# Hot_tub_PoE_RS485_Arduino.net
KiCad netlist of a schematic drawn in EAGLE
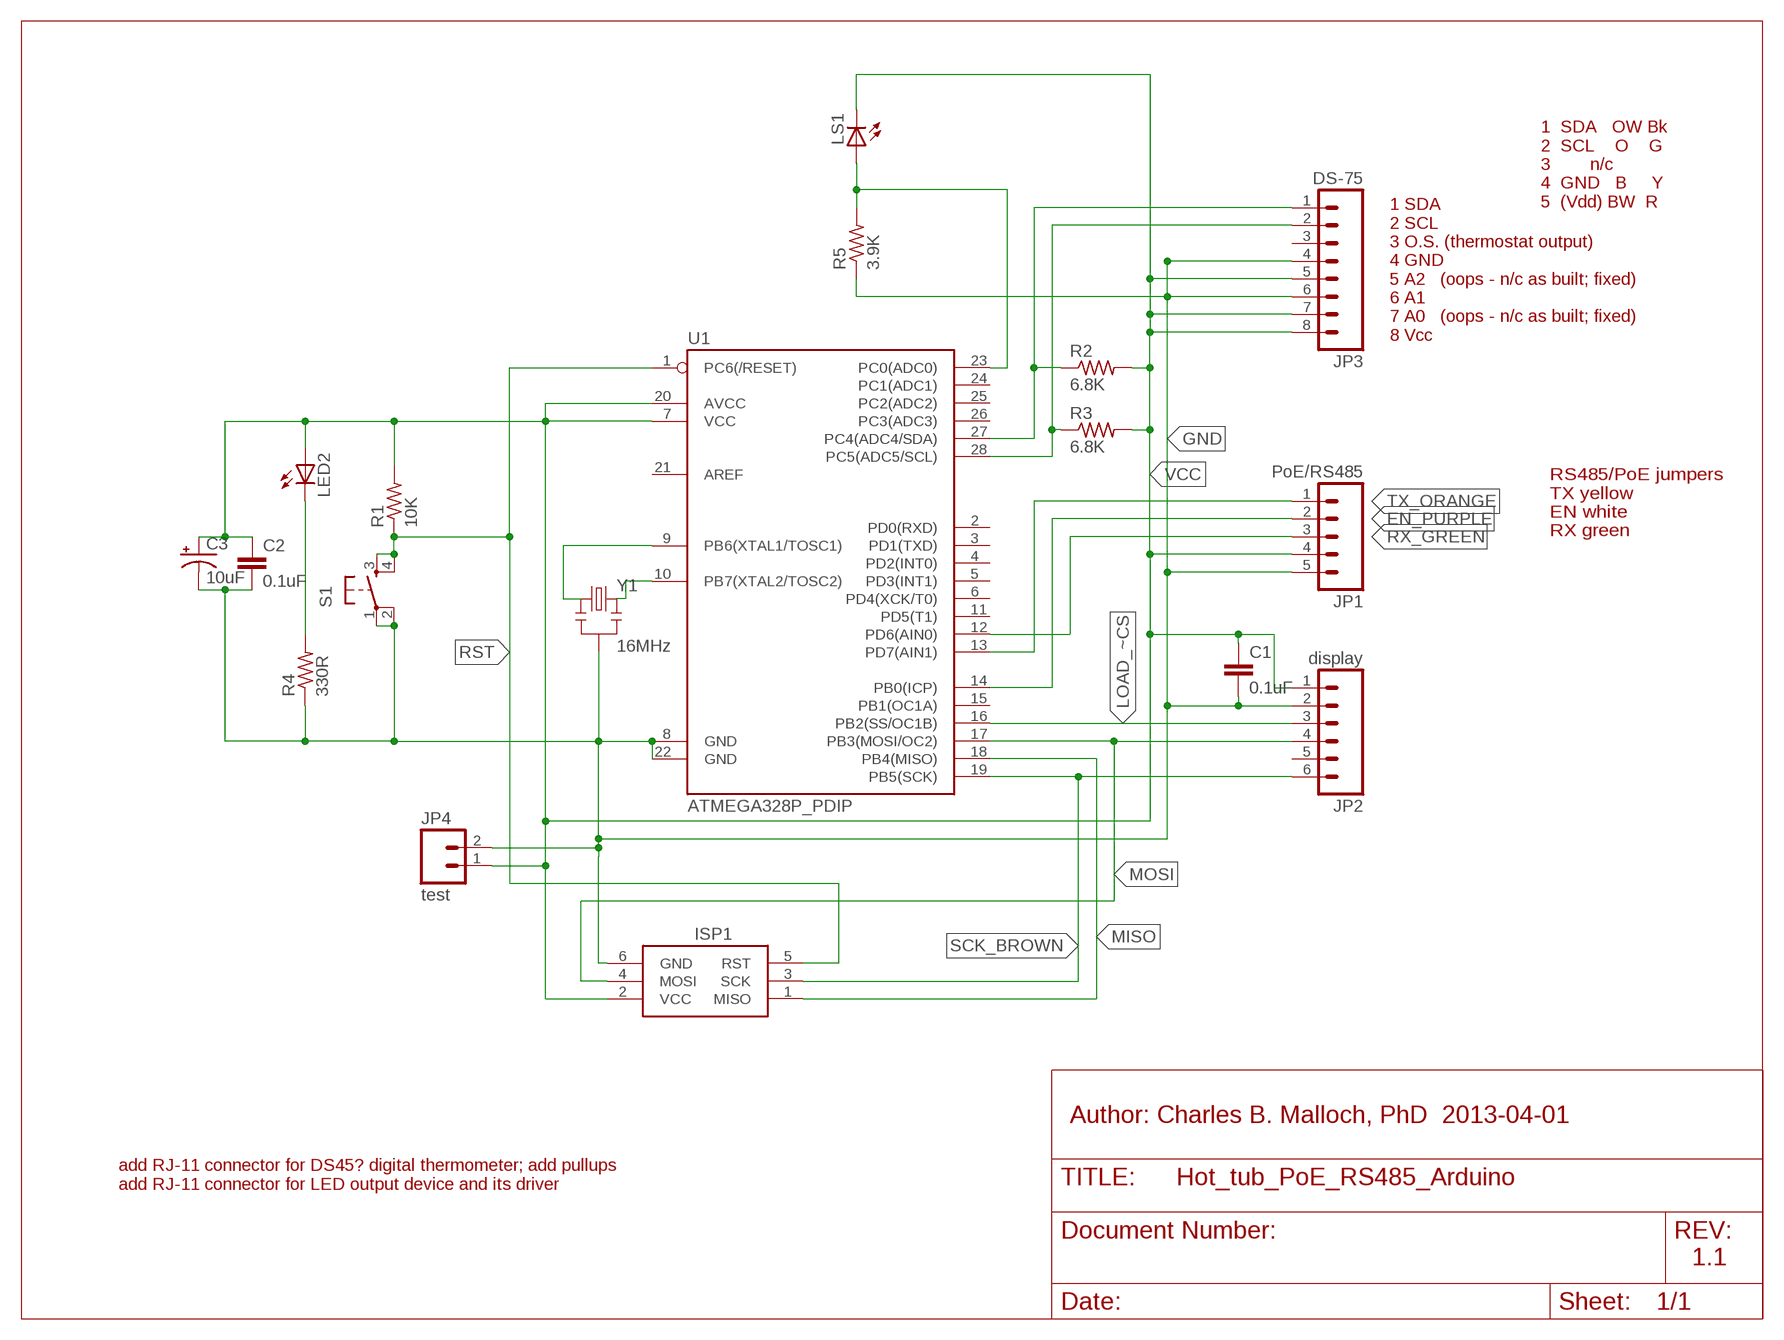
[diagram p0: schematic, sheet 1]

(export (version "E")
  (design (tool "Eeschema 10.0.6"))
  (components
    (comp (ref "C1")
      (value "0.1uF")
      (footprint "eagle-import:CAP-PTH-SMALL")
      (libsource (lib "eagle-import") (part "CAPPTH"))
    )
    (comp (ref "C2")
      (value "0.1uF")
      (footprint "eagle-import:CAP-PTH-SMALL")
      (libsource (lib "eagle-import") (part "CAPPTH"))
    )
    (comp (ref "C3")
      (value "10uF")
      (footprint "eagle-import:CPOL-RADIAL-10UF-25V")
      (libsource (lib "eagle-import") (part "CAP_POLPTH2"))
    )
    (comp (ref "ISP1")
      (value "AVRISP-6")
      (footprint "eagle-import:AVRISP")
      (libsource (lib "eagle-import") (part "AVRISP-6"))
    )
    (comp (ref "JP1")
      (value "PoE/RS485")
      (footprint "eagle-import:1X05_LOCK_LONGPADS")
      (libsource (lib "eagle-import") (part "M05LOCK_LONGPADS"))
    )
    (comp (ref "JP2")
      (value "display")
      (footprint "eagle-import:1X06_LOCK_LONGPADS")
      (libsource (lib "eagle-import") (part "M06LOCK_LONGPADS"))
    )
    (comp (ref "JP3")
      (value "DS-75")
      (footprint "eagle-import:1X08_LOCK_LONGPADS")
      (libsource (lib "eagle-import") (part "M08LOCK_LONGPADS"))
    )
    (comp (ref "JP4")
      (value "test")
      (footprint "eagle-import:1X02_LOCK_LONGPADS")
      (libsource (lib "eagle-import") (part "M02LOCK_LONGPADS"))
    )
    (comp (ref "LED2")
      (value "LED5MM")
      (footprint "eagle-import:LED5MM")
      (libsource (lib "eagle-import") (part "LED5MM"))
    )
    (comp (ref "LS1")
      (value "LED5MM")
      (footprint "eagle-import:LED5MM")
      (libsource (lib "eagle-import") (part "LED5MM"))
    )
    (comp (ref "R1")
      (value "10K")
      (footprint "eagle-import:0204_5")
      (libsource (lib "eagle-import") (part "R-US_0204/5"))
    )
    (comp (ref "R2")
      (value "6.8K")
      (footprint "eagle-import:0207_10")
      (libsource (lib "eagle-import") (part "resistor_R-US_0207/10"))
    )
    (comp (ref "R3")
      (value "6.8K")
      (footprint "eagle-import:0207_10")
      (libsource (lib "eagle-import") (part "resistor_R-US_0207/10"))
    )
    (comp (ref "R4")
      (value "330R")
      (footprint "eagle-import:0207_10")
      (libsource (lib "eagle-import") (part "resistor_R-US_0207/10"))
    )
    (comp (ref "R5")
      (value "3.9K")
      (footprint "eagle-import:0207_10")
      (libsource (lib "eagle-import") (part "resistor_R-US_0207/10"))
    )
    (comp (ref "S1")
      (value "TAC_SWITCHPTH")
      (footprint "eagle-import:TACTILE-PTH")
      (libsource (lib "eagle-import") (part "TAC_SWITCHPTH"))
    )
    (comp (ref "U1")
      (value "ATMEGA328P_PDIP")
      (footprint "eagle-import:DIL28-3")
      (libsource (lib "eagle-import") (part "ATMEGA328P_PDIP"))
    )
    (comp (ref "Y1")
      (value "16MHz")
      (footprint "eagle-import:RESONATOR-PTH")
      (libsource (lib "eagle-import") (part "RESONATORPTH"))
    )
  )
  (nets
    (net (code "1") (name "/LOAD_~{CS}") (class "Default")
      (node (ref "JP2") (pin "3") (pinfunction "3_3") (pintype "passive"))
      (node (ref "U1") (pin "16") (pinfunction "PB2(SS/OC1B)_16") (pintype "bidirectional"))
    )
    (net (code "2") (name "EN_PURPLE") (class "Default")
      (node (ref "JP1") (pin "2") (pinfunction "2_2") (pintype "passive"))
      (node (ref "U1") (pin "14") (pinfunction "PB0(ICP)_14") (pintype "bidirectional"))
    )
    (net (code "3") (name "GND") (class "Default")
      (node (ref "C1") (pin "2") (pinfunction "2_2") (pintype "passive"))
      (node (ref "C2") (pin "2") (pinfunction "2_2") (pintype "passive"))
      (node (ref "C3") (pin "2") (pinfunction "-_2") (pintype "passive"))
      (node (ref "ISP1") (pin "6") (pinfunction "GND_6") (pintype "power_in"))
      (node (ref "JP1") (pin "5") (pinfunction "5_5") (pintype "passive"))
      (node (ref "JP2") (pin "2") (pinfunction "2_2") (pintype "passive"))
      (node (ref "JP3") (pin "4") (pinfunction "4_4") (pintype "passive"))
      (node (ref "JP3") (pin "6") (pinfunction "6_6") (pintype "passive"))
      (node (ref "JP4") (pin "2") (pinfunction "2_2") (pintype "passive"))
      (node (ref "R4") (pin "1") (pinfunction "1_1") (pintype "passive"))
      (node (ref "R5") (pin "1") (pinfunction "1_1") (pintype "passive"))
      (node (ref "S1") (pin "1") (pinfunction "1_1") (pintype "passive"))
      (node (ref "S1") (pin "2") (pinfunction "2_2") (pintype "passive"))
      (node (ref "U1") (pin "22") (pinfunction "GND_22") (pintype "bidirectional"))
      (node (ref "U1") (pin "8") (pinfunction "GND_8") (pintype "bidirectional"))
      (node (ref "Y1") (pin "2") (pinfunction "2_2") (pintype "passive"))
    )
    (net (code "4") (name "MISO") (class "Default")
      (node (ref "ISP1") (pin "1") (pinfunction "MISO_1") (pintype "input"))
      (node (ref "U1") (pin "18") (pinfunction "PB4(MISO)_18") (pintype "bidirectional"))
    )
    (net (code "5") (name "MOSI") (class "Default")
      (node (ref "ISP1") (pin "4") (pinfunction "MOSI_4") (pintype "output"))
      (node (ref "JP2") (pin "4") (pinfunction "4_4") (pintype "passive"))
      (node (ref "U1") (pin "17") (pinfunction "PB3(MOSI/OC2)_17") (pintype "bidirectional"))
    )
    (net (code "6") (name "Net-(LED2-C)") (class "Default")
      (node (ref "LED2") (pin "K") (pinfunction "C_K") (pintype "passive"))
      (node (ref "R4") (pin "2") (pinfunction "2_2") (pintype "passive"))
    )
    (net (code "7") (name "Net-(U1-PB6(XTAL1{slash}TOSC1))") (class "Default")
      (node (ref "U1") (pin "9") (pinfunction "PB6(XTAL1/TOSC1)_9") (pintype "bidirectional"))
      (node (ref "Y1") (pin "1") (pinfunction "1_1") (pintype "passive"))
    )
    (net (code "8") (name "Net-(U1-PB7(XTAL2{slash}TOSC2))") (class "Default")
      (node (ref "U1") (pin "10") (pinfunction "PB7(XTAL2/TOSC2)_10") (pintype "bidirectional"))
      (node (ref "Y1") (pin "3") (pinfunction "3_3") (pintype "passive"))
    )
    (net (code "9") (name "Net-(U1-PC0(ADC0))") (class "Default")
      (node (ref "LS1") (pin "A") (pinfunction "A_A") (pintype "passive"))
      (node (ref "R5") (pin "2") (pinfunction "2_2") (pintype "passive"))
      (node (ref "U1") (pin "23") (pinfunction "PC0(ADC0)_23") (pintype "bidirectional"))
    )
    (net (code "10") (name "Net-(U1-PC4(ADC4{slash}SDA))") (class "Default")
      (node (ref "JP3") (pin "1") (pinfunction "1_1") (pintype "passive"))
      (node (ref "R2") (pin "1") (pinfunction "1_1") (pintype "passive"))
      (node (ref "U1") (pin "27") (pinfunction "PC4(ADC4/SDA)_27") (pintype "bidirectional"))
    )
    (net (code "11") (name "Net-(U1-PC5(ADC5{slash}SCL))") (class "Default")
      (node (ref "JP3") (pin "2") (pinfunction "2_2") (pintype "passive"))
      (node (ref "R3") (pin "1") (pinfunction "1_1") (pintype "passive"))
      (node (ref "U1") (pin "28") (pinfunction "PC5(ADC5/SCL)_28") (pintype "bidirectional"))
    )
    (net (code "12") (name "RST") (class "Default")
      (node (ref "ISP1") (pin "5") (pinfunction "RST_5") (pintype "output"))
      (node (ref "R1") (pin "1") (pinfunction "1_1") (pintype "passive"))
      (node (ref "S1") (pin "3") (pinfunction "3_3") (pintype "passive"))
      (node (ref "S1") (pin "4") (pinfunction "4_4") (pintype "passive"))
      (node (ref "U1") (pin "1") (pinfunction "PC6(/RESET)_1") (pintype "bidirectional"))
    )
    (net (code "13") (name "RX_GREEN") (class "Default")
      (node (ref "JP1") (pin "3") (pinfunction "3_3") (pintype "passive"))
      (node (ref "U1") (pin "12") (pinfunction "PD6(AIN0)_12") (pintype "bidirectional"))
    )
    (net (code "14") (name "SCK_BROWN") (class "Default")
      (node (ref "ISP1") (pin "3") (pinfunction "SCK_3") (pintype "output"))
      (node (ref "JP2") (pin "6") (pinfunction "6_6") (pintype "passive"))
      (node (ref "U1") (pin "19") (pinfunction "PB5(SCK)_19") (pintype "bidirectional"))
    )
    (net (code "15") (name "TX_ORANGE") (class "Default")
      (node (ref "JP1") (pin "1") (pinfunction "1_1") (pintype "passive"))
      (node (ref "U1") (pin "13") (pinfunction "PD7(AIN1)_13") (pintype "bidirectional"))
    )
    (net (code "16") (name "VCC") (class "Default")
      (node (ref "C1") (pin "1") (pinfunction "1_1") (pintype "passive"))
      (node (ref "C2") (pin "1") (pinfunction "1_1") (pintype "passive"))
      (node (ref "C3") (pin "1") (pinfunction "+_1") (pintype "passive"))
      (node (ref "ISP1") (pin "2") (pinfunction "VCC_2") (pintype "power_in"))
      (node (ref "JP1") (pin "4") (pinfunction "4_4") (pintype "passive"))
      (node (ref "JP2") (pin "1") (pinfunction "1_1") (pintype "passive"))
      (node (ref "JP3") (pin "5") (pinfunction "5_5") (pintype "passive"))
      (node (ref "JP3") (pin "7") (pinfunction "7_7") (pintype "passive"))
      (node (ref "JP3") (pin "8") (pinfunction "8_8") (pintype "passive"))
      (node (ref "JP4") (pin "1") (pinfunction "1_1") (pintype "passive"))
      (node (ref "LED2") (pin "A") (pinfunction "A_A") (pintype "passive"))
      (node (ref "LS1") (pin "K") (pinfunction "C_K") (pintype "passive"))
      (node (ref "R1") (pin "2") (pinfunction "2_2") (pintype "passive"))
      (node (ref "R2") (pin "2") (pinfunction "2_2") (pintype "passive"))
      (node (ref "R3") (pin "2") (pinfunction "2_2") (pintype "passive"))
      (node (ref "U1") (pin "20") (pinfunction "AVCC_20") (pintype "bidirectional"))
      (node (ref "U1") (pin "7") (pinfunction "VCC_7") (pintype "bidirectional"))
    )
    (net (code "17") (name "unconnected-(JP2-Pad5)") (class "Default")
      (node (ref "JP2") (pin "5") (pinfunction "5_5") (pintype "passive"))
    )
    (net (code "18") (name "unconnected-(JP3-Pad3)") (class "Default")
      (node (ref "JP3") (pin "3") (pinfunction "3_3") (pintype "passive"))
    )
    (net (code "19") (name "unconnected-(U1-AREF-Pad21)") (class "Default")
      (node (ref "U1") (pin "21") (pinfunction "AREF_21") (pintype "bidirectional"))
    )
    (net (code "20") (name "unconnected-(U1-PB1(OC1A)-Pad15)") (class "Default")
      (node (ref "U1") (pin "15") (pinfunction "PB1(OC1A)_15") (pintype "bidirectional"))
    )
    (net (code "21") (name "unconnected-(U1-PC1(ADC1)-Pad24)") (class "Default")
      (node (ref "U1") (pin "24") (pinfunction "PC1(ADC1)_24") (pintype "bidirectional"))
    )
    (net (code "22") (name "unconnected-(U1-PC2(ADC2)-Pad25)") (class "Default")
      (node (ref "U1") (pin "25") (pinfunction "PC2(ADC2)_25") (pintype "bidirectional"))
    )
    (net (code "23") (name "unconnected-(U1-PC3(ADC3)-Pad26)") (class "Default")
      (node (ref "U1") (pin "26") (pinfunction "PC3(ADC3)_26") (pintype "bidirectional"))
    )
    (net (code "24") (name "unconnected-(U1-PD0(RXD)-Pad2)") (class "Default")
      (node (ref "U1") (pin "2") (pinfunction "PD0(RXD)_2") (pintype "bidirectional"))
    )
    (net (code "25") (name "unconnected-(U1-PD1(TXD)-Pad3)") (class "Default")
      (node (ref "U1") (pin "3") (pinfunction "PD1(TXD)_3") (pintype "bidirectional"))
    )
    (net (code "26") (name "unconnected-(U1-PD2(INT0)-Pad4)") (class "Default")
      (node (ref "U1") (pin "4") (pinfunction "PD2(INT0)_4") (pintype "bidirectional"))
    )
    (net (code "27") (name "unconnected-(U1-PD3(INT1)-Pad5)") (class "Default")
      (node (ref "U1") (pin "5") (pinfunction "PD3(INT1)_5") (pintype "bidirectional"))
    )
    (net (code "28") (name "unconnected-(U1-PD4(XCK{slash}T0)-Pad6)") (class "Default")
      (node (ref "U1") (pin "6") (pinfunction "PD4(XCK/T0)_6") (pintype "bidirectional"))
    )
    (net (code "29") (name "unconnected-(U1-PD5(T1)-Pad11)") (class "Default")
      (node (ref "U1") (pin "11") (pinfunction "PD5(T1)_11") (pintype "bidirectional"))
    )
  )
)
